# Side_LongE.net
KiCad netlist of a schematic drawn in EAGLE
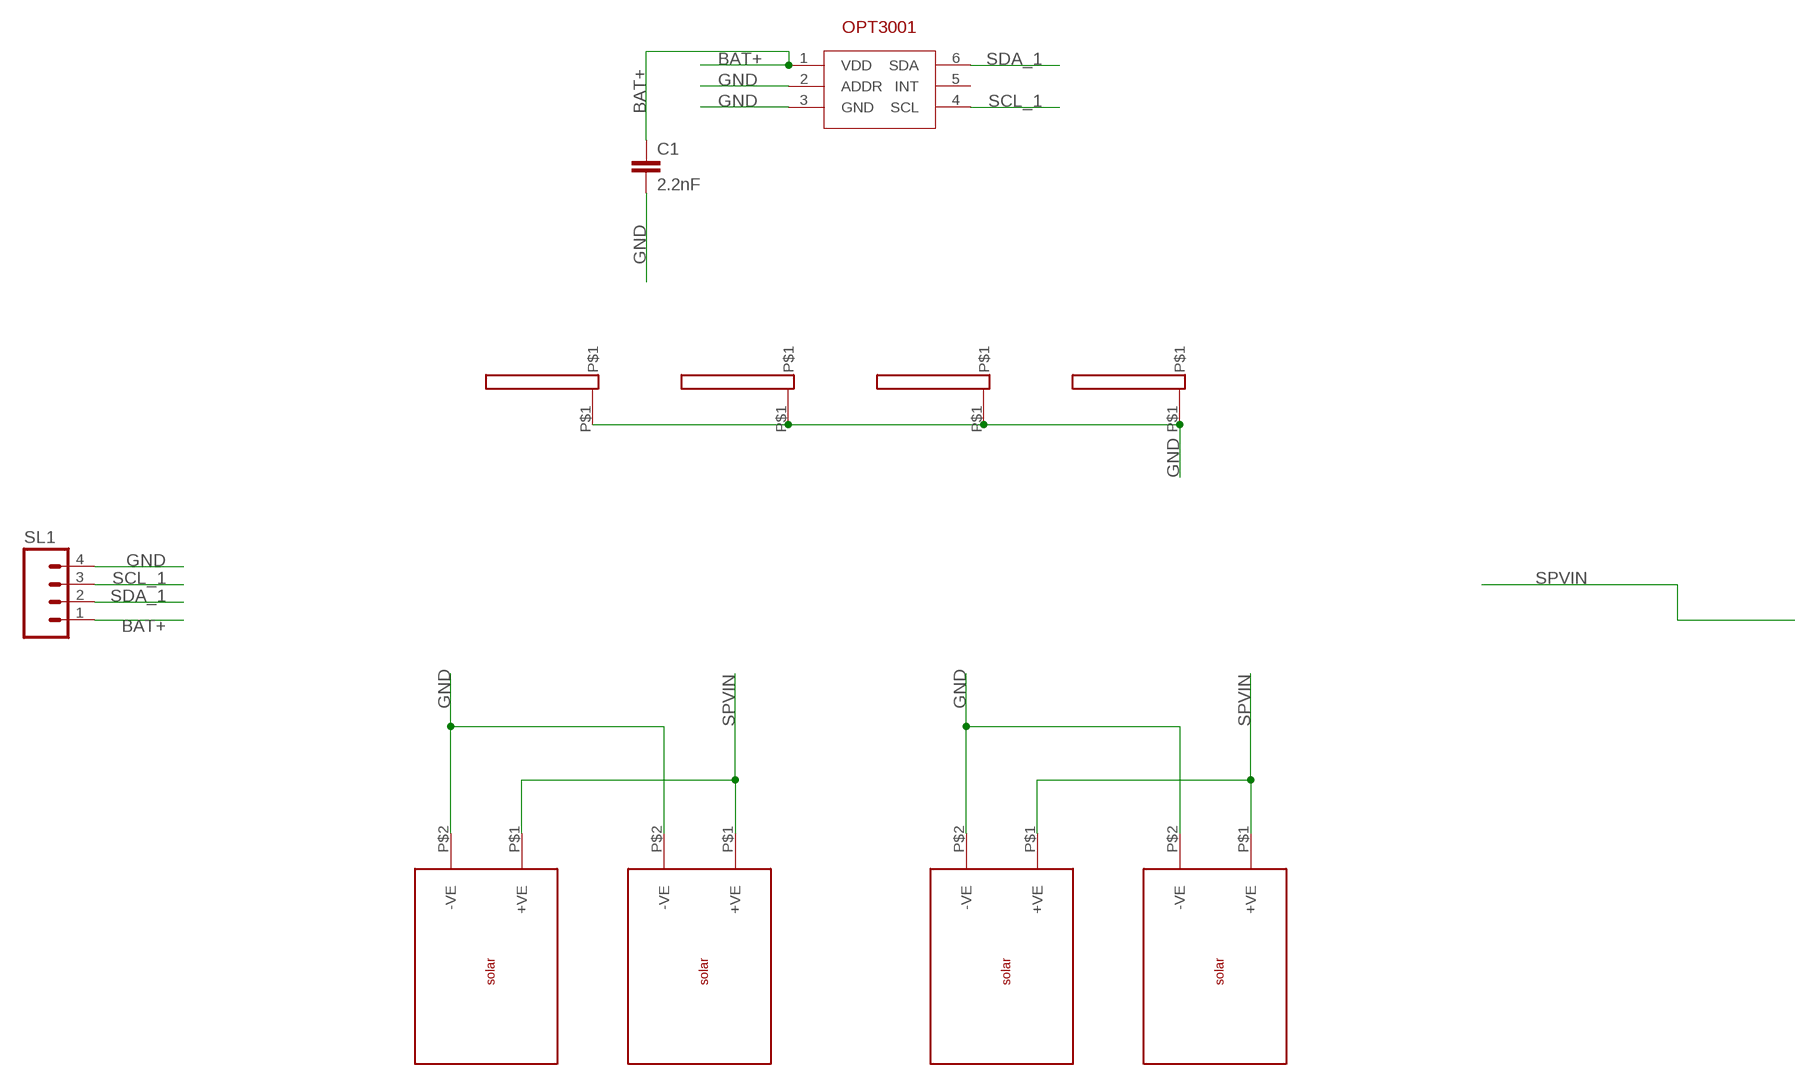
[diagram p0: schematic, sheet 1, part 1 of 2]
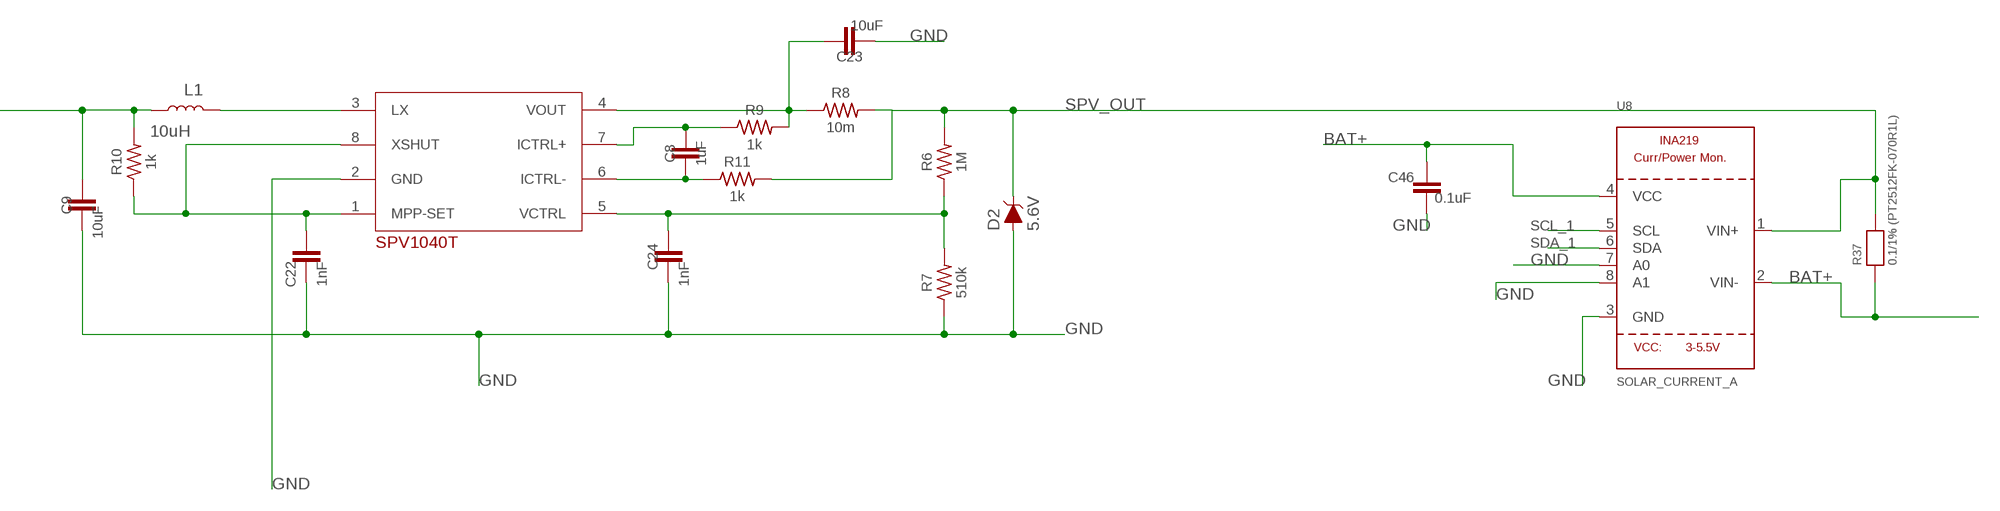
[diagram p1: schematic, sheet 1, part 2 of 2]

(export (version "E")
  (design (tool "Eeschema 10.0.6"))
  (components
    (comp (ref "C1")
      (value "2.2nF")
      (footprint "eagle-import:0603")
      (libsource (lib "eagle-import") (part "2.2NF/2200PF-0603-50V-10%"))
    )
    (comp (ref "C8")
      (value "1uF")
      (footprint "eagle-import:0603")
      (libsource (lib "eagle-import") (part "10UF-0603-6.3V-20%"))
    )
    (comp (ref "C9")
      (value "10uF")
      (footprint "eagle-import:0603")
      (libsource (lib "eagle-import") (part "10UF-0603-6.3V-20%"))
    )
    (comp (ref "C22")
      (value "1nF")
      (footprint "eagle-import:0603")
      (libsource (lib "eagle-import") (part "10UF-0603-6.3V-20%"))
    )
    (comp (ref "C23")
      (value "10uF")
      (footprint "eagle-import:0603")
      (libsource (lib "eagle-import") (part "10UF-0603-6.3V-20%"))
    )
    (comp (ref "C24")
      (value "1nF")
      (footprint "eagle-import:0603")
      (libsource (lib "eagle-import") (part "10UF-0603-6.3V-20%"))
    )
    (comp (ref "C46")
      (value "0.1uF")
      (footprint "eagle-import:0603")
      (libsource (lib "eagle-import") (part "10UF-0603-6.3V-20%"))
    )
    (comp (ref "D2")
      (value "5.6V")
      (footprint "eagle-import:SOD-323")
      (libsource (lib "eagle-import") (part "DIODE-ZENER-MMSZ5232BS"))
    )
    (comp (ref "L1")
      (value "10uH")
      (footprint "eagle-import:0603")
      (libsource (lib "eagle-import") (part "INDUCTOR-0603-33NH"))
    )
    (comp (ref "R6")
      (value "1M")
      (footprint "eagle-import:RES_0603")
      (fields
        (field (name "DIGIKEY_PART_NUMBER") "311-0.0GRTR-ND")
        (field (name "MANUFACTURER") "Yageo")
        (field (name "MPN") "RC0603JR-070RL")
        (field (name "CREATED_BY") "PCBLayout.com")
      )
      (libsource (lib "eagle-import") (part "RC0603JR-070RL"))
    )
    (comp (ref "R7")
      (value "510k")
      (footprint "eagle-import:RES_0603")
      (fields
        (field (name "DIGIKEY_PART_NUMBER") "311-0.0GRTR-ND")
        (field (name "MANUFACTURER") "Yageo")
        (field (name "MPN") "RC0603JR-070RL")
        (field (name "CREATED_BY") "PCBLayout.com")
      )
      (libsource (lib "eagle-import") (part "RC0603JR-070RL"))
    )
    (comp (ref "R8")
      (value "10m")
      (footprint "eagle-import:RES_0603")
      (fields
        (field (name "DIGIKEY_PART_NUMBER") "311-0.0GRTR-ND")
        (field (name "MANUFACTURER") "Yageo")
        (field (name "MPN") "RC0603JR-070RL")
        (field (name "CREATED_BY") "PCBLayout.com")
      )
      (libsource (lib "eagle-import") (part "RC0603JR-070RL"))
    )
    (comp (ref "R9")
      (value "1k")
      (footprint "eagle-import:RES_0603")
      (fields
        (field (name "DIGIKEY_PART_NUMBER") "311-0.0GRTR-ND")
        (field (name "MANUFACTURER") "Yageo")
        (field (name "MPN") "RC0603JR-070RL")
        (field (name "CREATED_BY") "PCBLayout.com")
      )
      (libsource (lib "eagle-import") (part "RC0603JR-070RL"))
    )
    (comp (ref "R10")
      (value "1k")
      (footprint "eagle-import:RES_0603")
      (fields
        (field (name "DIGIKEY_PART_NUMBER") "311-0.0GRTR-ND")
        (field (name "MANUFACTURER") "Yageo")
        (field (name "MPN") "RC0603JR-070RL")
        (field (name "CREATED_BY") "PCBLayout.com")
      )
      (libsource (lib "eagle-import") (part "RC0603JR-070RL"))
    )
    (comp (ref "R11")
      (value "1k")
      (footprint "eagle-import:RES_0603")
      (fields
        (field (name "DIGIKEY_PART_NUMBER") "311-0.0GRTR-ND")
        (field (name "MANUFACTURER") "Yageo")
        (field (name "MPN") "RC0603JR-070RL")
        (field (name "CREATED_BY") "PCBLayout.com")
      )
      (libsource (lib "eagle-import") (part "RC0603JR-070RL"))
    )
    (comp (ref "R37")
      (value "0.1/1% (PT2512FK-070R1L)")
      (footprint "eagle-import:2512")
      (libsource (lib "eagle-import") (part "RESISTOR2512"))
    )
    (comp (ref "SL1")
      (value "M04")
      (footprint "eagle-import:04P")
      (libsource (lib "eagle-import") (part "M04"))
    )
    (comp (ref "SPV_A")
      (value "SPV1040T_")
      (footprint "eagle-import:SOP65P640X120-8N")
      (libsource (lib "eagle-import") (part "SPV1040T_"))
    )
    (comp (ref "U$1")
      (value "SOLAR_50_5_2")
      (footprint "eagle-import:FOOT")
      (libsource (lib "eagle-import") (part "SOLAR_50_5_2"))
    )
    (comp (ref "U$2")
      (value "SOLAR_50_5_2")
      (footprint "eagle-import:FOOT")
      (libsource (lib "eagle-import") (part "SOLAR_50_5_2"))
    )
    (comp (ref "U$3")
      (value "16X2")
      (footprint "eagle-import:16X2")
      (libsource (lib "eagle-import") (part "16X2"))
    )
    (comp (ref "U$4")
      (value "16X2")
      (footprint "eagle-import:16X2")
      (libsource (lib "eagle-import") (part "16X2"))
    )
    (comp (ref "U$5")
      (value "16X2")
      (footprint "eagle-import:16X2")
      (libsource (lib "eagle-import") (part "16X2"))
    )
    (comp (ref "U$6")
      (value "16X2")
      (footprint "eagle-import:16X2")
      (libsource (lib "eagle-import") (part "16X2"))
    )
    (comp (ref "U$7")
      (value "SOLAR_50_5_2")
      (footprint "eagle-import:FOOT")
      (libsource (lib "eagle-import") (part "SOLAR_50_5_2"))
    )
    (comp (ref "U$8")
      (value "SOLAR_50_5_2")
      (footprint "eagle-import:FOOT")
      (libsource (lib "eagle-import") (part "SOLAR_50_5_2"))
    )
    (comp (ref "U1")
      (value "SON65P200X200X65-7N")
      (footprint "eagle-import:SON65P200X200X65-7N")
      (fields (field (name "MANUFACTURER") "Maxim Integrated"))
      (libsource (lib "eagle-import") (part "SON65P200X200X65-7N"))
    )
    (comp (ref "U8")
      (value "SOLAR_CURRENT_A")
      (footprint "eagle-import:SOT23-8")
      (libsource (lib "eagle-import") (part "INA219"))
    )
  )
  (nets
    (net (code "1") (name "/BAT+") (class "Default")
      (node (ref "C1") (pin "1") (pinfunction "1_1") (pintype "passive"))
      (node (ref "C46") (pin "1") (pinfunction "1_1") (pintype "passive"))
      (node (ref "R37") (pin "1") (pinfunction "1_1") (pintype "passive"))
      (node (ref "SL1") (pin "1") (pinfunction "1_1") (pintype "passive"))
      (node (ref "U1") (pin "1") (pinfunction "VDD_1") (pintype "bidirectional"))
      (node (ref "U8") (pin "2") (pinfunction "VIN-_2") (pintype "bidirectional"))
      (node (ref "U8") (pin "4") (pinfunction "VCC_4") (pintype "bidirectional"))
    )
    (net (code "2") (name "/GND") (class "Default")
      (node (ref "C1") (pin "2") (pinfunction "2_2") (pintype "passive"))
      (node (ref "C22") (pin "2") (pinfunction "2_2") (pintype "passive"))
      (node (ref "C23") (pin "2") (pinfunction "2_2") (pintype "passive"))
      (node (ref "C24") (pin "2") (pinfunction "2_2") (pintype "passive"))
      (node (ref "C46") (pin "2") (pinfunction "2_2") (pintype "passive"))
      (node (ref "C9") (pin "2") (pinfunction "2_2") (pintype "passive"))
      (node (ref "D2") (pin "A") (pinfunction "A_A") (pintype "passive"))
      (node (ref "R7") (pin "1") (pinfunction "1_1") (pintype "passive"))
      (node (ref "SL1") (pin "4") (pinfunction "4_4") (pintype "passive"))
      (node (ref "SPV_A") (pin "2") (pinfunction "GND_2") (pintype "bidirectional"))
      (node (ref "U$1") (pin "P$2") (pinfunction "-VE_P$2") (pintype "bidirectional"))
      (node (ref "U$2") (pin "P$2") (pinfunction "-VE_P$2") (pintype "bidirectional"))
      (node (ref "U$3") (pin "P$1") (pinfunction "P$1_P$1") (pintype "bidirectional"))
      (node (ref "U$4") (pin "P$1") (pinfunction "P$1_P$1") (pintype "bidirectional"))
      (node (ref "U$5") (pin "P$1") (pinfunction "P$1_P$1") (pintype "bidirectional"))
      (node (ref "U$6") (pin "P$1") (pinfunction "P$1_P$1") (pintype "bidirectional"))
      (node (ref "U$7") (pin "P$2") (pinfunction "-VE_P$2") (pintype "bidirectional"))
      (node (ref "U$8") (pin "P$2") (pinfunction "-VE_P$2") (pintype "bidirectional"))
      (node (ref "U1") (pin "2") (pinfunction "ADDR_2") (pintype "bidirectional"))
      (node (ref "U1") (pin "3") (pinfunction "GND_3") (pintype "bidirectional"))
      (node (ref "U8") (pin "3") (pinfunction "GND_3") (pintype "bidirectional"))
      (node (ref "U8") (pin "7") (pinfunction "A0_7") (pintype "bidirectional"))
      (node (ref "U8") (pin "8") (pinfunction "A1_8") (pintype "bidirectional"))
    )
    (net (code "3") (name "/SCL_1") (class "Default")
      (node (ref "SL1") (pin "3") (pinfunction "3_3") (pintype "passive"))
      (node (ref "U1") (pin "4") (pinfunction "SCL_4") (pintype "bidirectional"))
      (node (ref "U8") (pin "5") (pinfunction "SCL_5") (pintype "bidirectional"))
    )
    (net (code "4") (name "/SDA_1") (class "Default")
      (node (ref "SL1") (pin "2") (pinfunction "2_2") (pintype "passive"))
      (node (ref "U1") (pin "6") (pinfunction "SDA_6") (pintype "bidirectional"))
      (node (ref "U8") (pin "6") (pinfunction "SDA_6") (pintype "bidirectional"))
    )
    (net (code "5") (name "/SPVIN") (class "Default")
      (node (ref "C9") (pin "1") (pinfunction "1_1") (pintype "passive"))
      (node (ref "L1") (pin "1") (pinfunction "1_1") (pintype "passive"))
      (node (ref "R10") (pin "2") (pinfunction "2_2") (pintype "passive"))
      (node (ref "U$1") (pin "P$1") (pinfunction "+VE_P$1") (pintype "bidirectional"))
      (node (ref "U$2") (pin "P$1") (pinfunction "+VE_P$1") (pintype "bidirectional"))
      (node (ref "U$7") (pin "P$1") (pinfunction "+VE_P$1") (pintype "bidirectional"))
      (node (ref "U$8") (pin "P$1") (pinfunction "+VE_P$1") (pintype "bidirectional"))
    )
    (net (code "6") (name "/SPV_OUT") (class "Default")
      (node (ref "D2") (pin "C") (pinfunction "C_C") (pintype "passive"))
      (node (ref "R11") (pin "2") (pinfunction "2_2") (pintype "passive"))
      (node (ref "R37") (pin "2") (pinfunction "2_2") (pintype "passive"))
      (node (ref "R6") (pin "2") (pinfunction "2_2") (pintype "passive"))
      (node (ref "R8") (pin "2") (pinfunction "2_2") (pintype "passive"))
      (node (ref "U8") (pin "1") (pinfunction "VIN+_1") (pintype "bidirectional"))
    )
    (net (code "7") (name "Net-(SPV_A-ICTRL+)") (class "Default")
      (node (ref "C8") (pin "1") (pinfunction "1_1") (pintype "passive"))
      (node (ref "R9") (pin "1") (pinfunction "1_1") (pintype "passive"))
      (node (ref "SPV_A") (pin "7") (pinfunction "ICTRL+_7") (pintype "bidirectional"))
    )
    (net (code "8") (name "Net-(SPV_A-ICTRL-)") (class "Default")
      (node (ref "C8") (pin "2") (pinfunction "2_2") (pintype "passive"))
      (node (ref "R11") (pin "1") (pinfunction "1_1") (pintype "passive"))
      (node (ref "SPV_A") (pin "6") (pinfunction "ICTRL-_6") (pintype "bidirectional"))
    )
    (net (code "9") (name "Net-(SPV_A-LX)") (class "Default")
      (node (ref "L1") (pin "2") (pinfunction "2_2") (pintype "passive"))
      (node (ref "SPV_A") (pin "3") (pinfunction "LX_3") (pintype "bidirectional"))
    )
    (net (code "10") (name "Net-(SPV_A-MPP-SET)") (class "Default")
      (node (ref "C22") (pin "1") (pinfunction "1_1") (pintype "passive"))
      (node (ref "R10") (pin "1") (pinfunction "1_1") (pintype "passive"))
      (node (ref "SPV_A") (pin "1") (pinfunction "MPP-SET_1") (pintype "bidirectional"))
      (node (ref "SPV_A") (pin "8") (pinfunction "XSHUT_8") (pintype "bidirectional"))
    )
    (net (code "11") (name "Net-(SPV_A-VCTRL)") (class "Default")
      (node (ref "C24") (pin "1") (pinfunction "1_1") (pintype "passive"))
      (node (ref "R6") (pin "1") (pinfunction "1_1") (pintype "passive"))
      (node (ref "R7") (pin "2") (pinfunction "2_2") (pintype "passive"))
      (node (ref "SPV_A") (pin "5") (pinfunction "VCTRL_5") (pintype "bidirectional"))
    )
    (net (code "12") (name "Net-(SPV_A-VOUT)") (class "Default")
      (node (ref "C23") (pin "1") (pinfunction "1_1") (pintype "passive"))
      (node (ref "R8") (pin "1") (pinfunction "1_1") (pintype "passive"))
      (node (ref "R9") (pin "2") (pinfunction "2_2") (pintype "passive"))
      (node (ref "SPV_A") (pin "4") (pinfunction "VOUT_4") (pintype "bidirectional"))
    )
    (net (code "13") (name "unconnected-(U1-INT-Pad5)") (class "Default")
      (node (ref "U1") (pin "5") (pinfunction "INT_5") (pintype "bidirectional"))
    )
  )
)
